# IO_Peripherals.net
KiCad netlist of a schematic drawn in Altium Designer
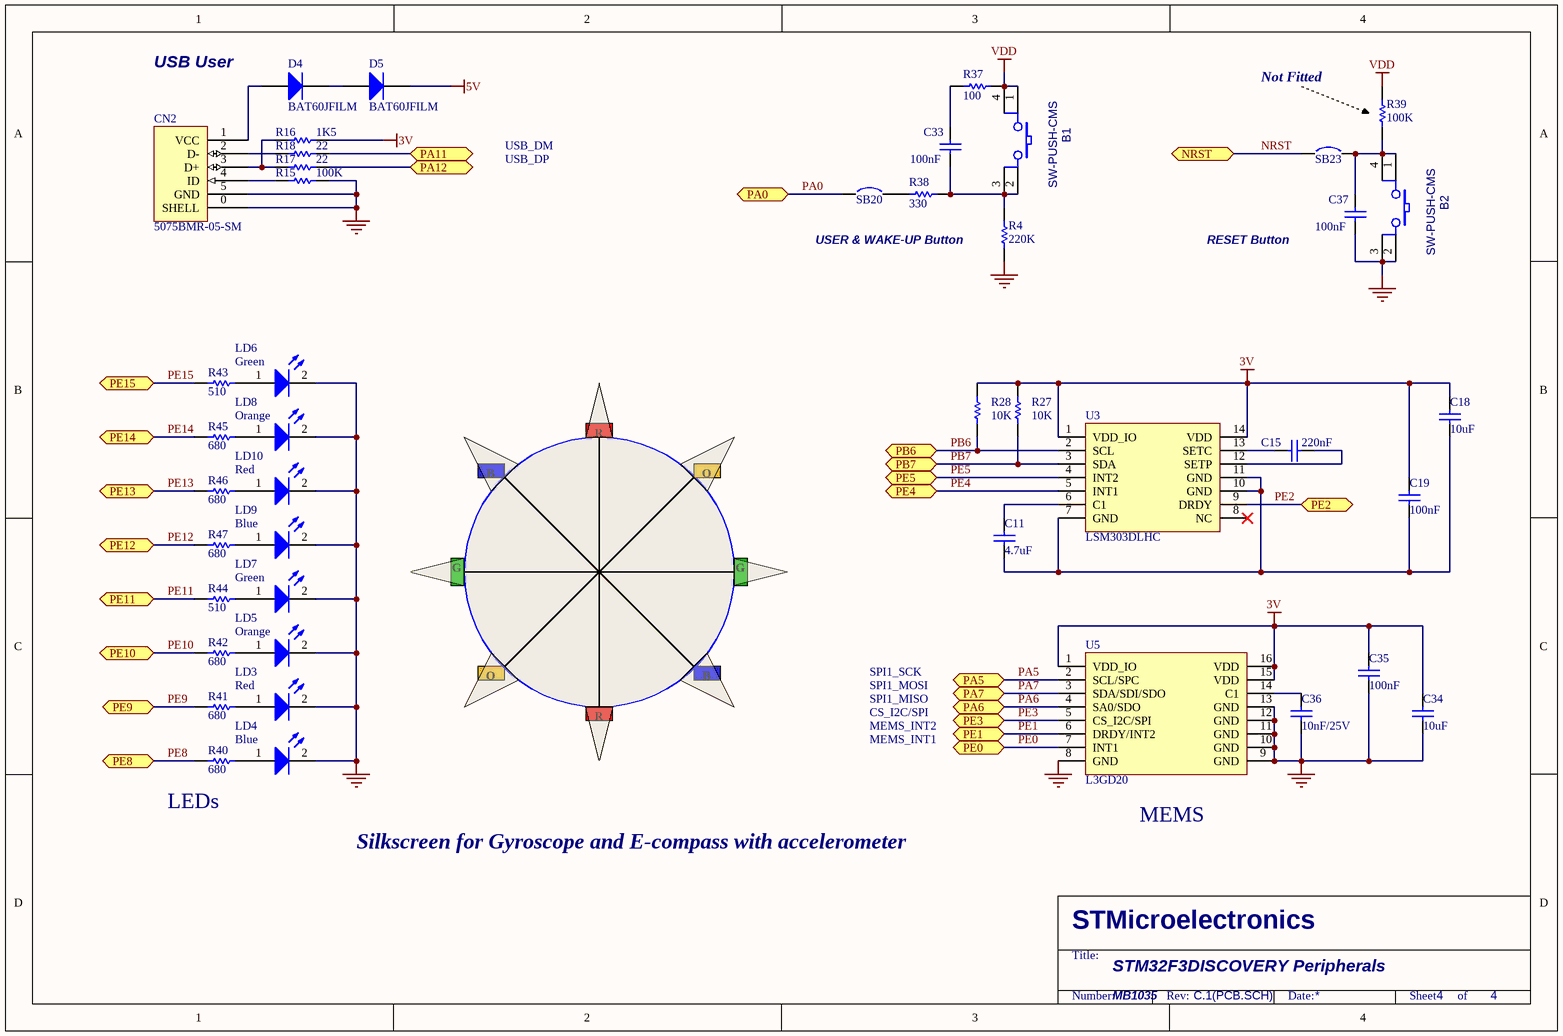
[diagram p0: IO Peripherals.SchDoc]

(export (version "E")
  (design (tool "Eeschema 10.0.6"))
  (components
    (comp (ref "B1")
      (value "SW-PUSH-CMS")
      (footprint "BP1CMS")
      (description "Non-Open Push-Button 0.1A 24V")
      (libsource (lib "MB913_1") (part "SW-PUSH-CMS"))
    )
    (comp (ref "B2")
      (value "SW-PUSH-CMS")
      (footprint "BP1CMS")
      (description "Non-Open Push-Button 0.1A 24V")
      (libsource (lib "MB913_1") (part "SW-PUSH-CMS"))
    )
    (comp (ref "C11")
      (value "4.7uF")
      (footprint "0603C")
      (description "Capacitor")
      (fields (field (name "PUBLISHER") "Altium Limited"))
      (libsource (lib "Miscellaneous Devices") (part "CAP"))
    )
    (comp (ref "C15")
      (value "220nF")
      (footprint "0603C")
      (description "Capacitor")
      (fields (field (name "PUBLISHER") "Altium Limited"))
      (libsource (lib "Miscellaneous Devices") (part "CAP"))
    )
    (comp (ref "C18")
      (value "10uF")
      (footprint "0603C")
      (description "Capacitor")
      (fields (field (name "PUBLISHER") "Altium Limited"))
      (libsource (lib "Miscellaneous Devices") (part "CAP"))
    )
    (comp (ref "C19")
      (value "100nF")
      (footprint "0603C")
      (description "Capacitor")
      (fields (field (name "PUBLISHER") "Altium Limited"))
      (libsource (lib "Miscellaneous Devices") (part "CAP"))
    )
    (comp (ref "C33")
      (value "100nF")
      (footprint "0603C")
      (description "Capacitor")
      (fields (field (name "PUBLISHER") "Altium Limited"))
      (libsource (lib "Miscellaneous Devices") (part "CAP"))
    )
    (comp (ref "C34")
      (value "10uF")
      (footprint "0603C")
      (description "Capacitor")
      (fields (field (name "PUBLISHER") "Altium Limited"))
      (libsource (lib "Miscellaneous Devices") (part "CAP"))
    )
    (comp (ref "C35")
      (value "100nF")
      (footprint "0603C")
      (description "Capacitor")
      (fields (field (name "PUBLISHER") "Altium Limited"))
      (libsource (lib "Miscellaneous Devices") (part "CAP"))
    )
    (comp (ref "C36")
      (value "10nF/25V")
      (footprint "0603C")
      (description "Capacitor")
      (fields (field (name "PUBLISHER") "Altium Limited"))
      (libsource (lib "Miscellaneous Devices") (part "CAP"))
    )
    (comp (ref "C37")
      (value "100nF")
      (footprint "0603C")
      (description "Capacitor")
      (fields (field (name "PUBLISHER") "Altium Limited"))
      (libsource (lib "Miscellaneous Devices") (part "CAP"))
    )
    (comp (ref "CN2")
      (value "5075BMR-05-SM")
      (footprint "USB-MINI-B-SMD")
      (libsource (lib "MCD_TOOLS") (part "USB-MINI-typeB connector"))
    )
    (comp (ref "D4")
      (value "BAT60JFILM")
      (footprint "SOD323/A")
      (fields (field (name "PUBLISHER") "Altium Limited"))
      (libsource (lib "MB997") (part "BAT60JFILM"))
    )
    (comp (ref "D5")
      (value "BAT60JFILM")
      (footprint "SOD323/A")
      (fields (field (name "PUBLISHER") "Altium Limited"))
      (libsource (lib "MB997") (part "BAT60JFILM"))
    )
    (comp (ref "LD3")
      (value "Red")
      (footprint "0603D")
      (description "Typical RED, GREEN, YELLOW, AMBER GaAs LED")
      (fields (field (name "PUBLISHER") "Altium Limited"))
      (libsource (lib "Miscellaneous Devices") (part "LED2"))
    )
    (comp (ref "LD4")
      (value "Blue")
      (footprint "0603D")
      (description "Typical RED, GREEN, YELLOW, AMBER GaAs LED")
      (fields (field (name "PUBLISHER") "Altium Limited"))
      (libsource (lib "Miscellaneous Devices") (part "LED2"))
    )
    (comp (ref "LD5")
      (value "Orange")
      (footprint "0603D")
      (description "Typical RED, GREEN, YELLOW, AMBER GaAs LED")
      (fields (field (name "PUBLISHER") "Altium Limited"))
      (libsource (lib "Miscellaneous Devices") (part "LED2"))
    )
    (comp (ref "LD6")
      (value "Green")
      (footprint "0603D")
      (description "Typical RED, GREEN, YELLOW, AMBER GaAs LED")
      (fields (field (name "PUBLISHER") "Altium Limited"))
      (libsource (lib "Miscellaneous Devices") (part "LED2"))
    )
    (comp (ref "LD7")
      (value "Green")
      (footprint "0603D")
      (description "Typical RED, GREEN, YELLOW, AMBER GaAs LED")
      (fields (field (name "PUBLISHER") "Altium Limited"))
      (libsource (lib "Miscellaneous Devices") (part "LED2"))
    )
    (comp (ref "LD8")
      (value "Orange")
      (footprint "0603D")
      (description "Typical RED, GREEN, YELLOW, AMBER GaAs LED")
      (fields (field (name "PUBLISHER") "Altium Limited"))
      (libsource (lib "Miscellaneous Devices") (part "LED2"))
    )
    (comp (ref "LD9")
      (value "Blue")
      (footprint "0603D")
      (description "Typical RED, GREEN, YELLOW, AMBER GaAs LED")
      (fields (field (name "PUBLISHER") "Altium Limited"))
      (libsource (lib "Miscellaneous Devices") (part "LED2"))
    )
    (comp (ref "LD10")
      (value "Red")
      (footprint "0603D")
      (description "Typical RED, GREEN, YELLOW, AMBER GaAs LED")
      (fields (field (name "PUBLISHER") "Altium Limited"))
      (libsource (lib "Miscellaneous Devices") (part "LED2"))
    )
    (comp (ref "R4")
      (value "220K")
      (description "Resistor")
      (fields (field (name "PUBLISHER") "Altium Limited"))
      (libsource (lib "Miscellaneous Devices") (part "res1"))
    )
    (comp (ref "R15")
      (value "100K")
      (footprint "0402R")
      (description "Resistor")
      (fields (field (name "PUBLISHER") "Altium Limited"))
      (libsource (lib "MB915_1") (part "res1"))
    )
    (comp (ref "R16")
      (value "1K5")
      (footprint "0402R")
      (description "Resistor")
      (fields (field (name "PUBLISHER") "Altium Limited"))
      (libsource (lib "MB915_1") (part "res1"))
    )
    (comp (ref "R17")
      (value "22")
      (footprint "0402R")
      (description "Resistor")
      (fields (field (name "PUBLISHER") "Altium Limited"))
      (libsource (lib "MB915_1") (part "res1"))
    )
    (comp (ref "R18")
      (value "22")
      (footprint "0402R")
      (description "Resistor")
      (fields (field (name "PUBLISHER") "Altium Limited"))
      (libsource (lib "MB915_1") (part "res1"))
    )
    (comp (ref "R27")
      (value "10K")
      (footprint "0402R")
      (description "Resistor")
      (fields (field (name "PUBLISHER") "Altium Limited"))
      (libsource (lib "Miscellaneous Devices") (part "res1"))
    )
    (comp (ref "R28")
      (value "10K")
      (footprint "0402R")
      (description "Resistor")
      (fields (field (name "PUBLISHER") "Altium Limited"))
      (libsource (lib "Miscellaneous Devices") (part "res1"))
    )
    (comp (ref "R37")
      (value "100")
      (footprint "0402R")
      (description "Resistor")
      (fields (field (name "PUBLISHER") "Altium Limited"))
      (libsource (lib "Miscellaneous Devices") (part "res1"))
    )
    (comp (ref "R38")
      (value "330")
      (footprint "0402R")
      (description "Resistor")
      (fields (field (name "PUBLISHER") "Altium Limited"))
      (libsource (lib "Miscellaneous Devices") (part "res1"))
    )
    (comp (ref "R39")
      (value "100K")
      (footprint "0402R")
      (description "Resistor")
      (fields (field (name "PUBLISHER") "Altium Limited"))
      (libsource (lib "Miscellaneous Devices") (part "res1"))
    )
    (comp (ref "R40")
      (value "680")
      (footprint "0603R")
      (description "Resistor")
      (fields (field (name "PUBLISHER") "Altium Limited"))
      (libsource (lib "Miscellaneous Devices") (part "Res1"))
    )
    (comp (ref "R41")
      (value "680")
      (footprint "0603R")
      (description "Resistor")
      (fields (field (name "PUBLISHER") "Altium Limited"))
      (libsource (lib "Miscellaneous Devices") (part "Res1"))
    )
    (comp (ref "R42")
      (value "680")
      (footprint "0603R")
      (description "Resistor")
      (fields (field (name "PUBLISHER") "Altium Limited"))
      (libsource (lib "Miscellaneous Devices") (part "Res1"))
    )
    (comp (ref "R43")
      (value "510")
      (footprint "0603R")
      (description "Resistor")
      (fields (field (name "PUBLISHER") "Altium Limited"))
      (libsource (lib "Miscellaneous Devices") (part "Res1"))
    )
    (comp (ref "R44")
      (value "510")
      (footprint "0603R")
      (description "Resistor")
      (fields (field (name "PUBLISHER") "Altium Limited"))
      (libsource (lib "Miscellaneous Devices") (part "Res1"))
    )
    (comp (ref "R45")
      (value "680")
      (footprint "0603R")
      (description "Resistor")
      (fields (field (name "PUBLISHER") "Altium Limited"))
      (libsource (lib "Miscellaneous Devices") (part "Res1"))
    )
    (comp (ref "R46")
      (value "680")
      (footprint "0603R")
      (description "Resistor")
      (fields (field (name "PUBLISHER") "Altium Limited"))
      (libsource (lib "Miscellaneous Devices") (part "Res1"))
    )
    (comp (ref "R47")
      (value "680")
      (footprint "0603R")
      (description "Resistor")
      (fields (field (name "PUBLISHER") "Altium Limited"))
      (libsource (lib "Miscellaneous Devices") (part "Res1"))
    )
    (comp (ref "SB20")
      (value "Circuit Breaker")
      (footprint "JP2_SMD")
      (fields (field (name "PUBLISHER") "Altium Limited"))
      (libsource (lib "MB915") (part "Circuit Breaker"))
    )
    (comp (ref "SB23")
      (value "Circuit Breaker")
      (footprint "JP2_SMD")
      (fields (field (name "PUBLISHER") "Altium Limited"))
      (libsource (lib "MB915") (part "Circuit Breaker"))
    )
    (comp (ref "U3")
      (value "LSM303DLHC")
      (footprint "LGA14")
      (description "Ultra compact high performance e-compass 3D accelerometer and 3D magnetometer module")
      (libsource (lib "MCD_TOOLS") (part "LSM303DLHC"))
    )
    (comp (ref "U5")
      (value "L3GD20")
      (footprint "LGA16")
      (description "MEMS motion sensor three-axis digital output gyroscopeelerometer")
      (libsource (lib "MCD_TOOLS") (part "L3GD20"))
    )
  )
  (nets
    (net (code "1") (name "/NRST") (class "Default")
      (node (ref "SB23") (pin "1") (pinfunction "1_1") (pintype "passive"))
    )
    (net (code "2") (name "/PA0") (class "Default")
      (node (ref "SB20") (pin "1") (pinfunction "1_1") (pintype "passive"))
    )
    (net (code "3") (name "/PA5") (class "Default")
      (node (ref "U5") (pin "2") (pinfunction "SCL/SPC_2") (pintype "passive"))
    )
    (net (code "4") (name "/PA6") (class "Default")
      (node (ref "U5") (pin "4") (pinfunction "SA0/SDO_4") (pintype "passive"))
    )
    (net (code "5") (name "/PA7") (class "Default")
      (node (ref "U5") (pin "3") (pinfunction "SDA/SDI/SDO_3") (pintype "passive"))
    )
    (net (code "6") (name "/PA11") (class "Default")
      (node (ref "R18") (pin "2") (pinfunction "2_2") (pintype "passive"))
    )
    (net (code "7") (name "/PA12") (class "Default")
      (node (ref "R17") (pin "2") (pinfunction "2_2") (pintype "passive"))
    )
    (net (code "8") (name "/PB6") (class "Default")
      (node (ref "R28") (pin "2") (pinfunction "2_2") (pintype "passive"))
      (node (ref "U3") (pin "2") (pinfunction "SCL_2") (pintype "passive"))
    )
    (net (code "9") (name "/PB7") (class "Default")
      (node (ref "R27") (pin "2") (pinfunction "2_2") (pintype "passive"))
      (node (ref "U3") (pin "3") (pinfunction "SDA_3") (pintype "passive"))
    )
    (net (code "10") (name "/PE0") (class "Default")
      (node (ref "U5") (pin "7") (pinfunction "INT1_7") (pintype "passive"))
    )
    (net (code "11") (name "/PE1") (class "Default")
      (node (ref "U5") (pin "6") (pinfunction "DRDY/INT2_6") (pintype "passive"))
    )
    (net (code "12") (name "/PE2") (class "Default")
      (node (ref "U3") (pin "9") (pinfunction "DRDY_9") (pintype "passive"))
    )
    (net (code "13") (name "/PE3") (class "Default")
      (node (ref "U5") (pin "5") (pinfunction "CS_I2C/SPI_5") (pintype "passive"))
    )
    (net (code "14") (name "/PE4") (class "Default")
      (node (ref "U3") (pin "5") (pinfunction "INT1_5") (pintype "passive"))
    )
    (net (code "15") (name "/PE5") (class "Default")
      (node (ref "U3") (pin "4") (pinfunction "INT2_4") (pintype "passive"))
    )
    (net (code "16") (name "/PE8") (class "Default")
      (node (ref "R40") (pin "2") (pinfunction "2_2") (pintype "passive"))
    )
    (net (code "17") (name "/PE9") (class "Default")
      (node (ref "R41") (pin "2") (pinfunction "2_2") (pintype "passive"))
    )
    (net (code "18") (name "/PE10") (class "Default")
      (node (ref "R42") (pin "2") (pinfunction "2_2") (pintype "passive"))
    )
    (net (code "19") (name "/PE11") (class "Default")
      (node (ref "R44") (pin "2") (pinfunction "2_2") (pintype "passive"))
    )
    (net (code "20") (name "/PE12") (class "Default")
      (node (ref "R47") (pin "2") (pinfunction "2_2") (pintype "passive"))
    )
    (net (code "21") (name "/PE13") (class "Default")
      (node (ref "R46") (pin "2") (pinfunction "2_2") (pintype "passive"))
    )
    (net (code "22") (name "/PE14") (class "Default")
      (node (ref "R45") (pin "2") (pinfunction "2_2") (pintype "passive"))
    )
    (net (code "23") (name "/PE15") (class "Default")
      (node (ref "R43") (pin "2") (pinfunction "2_2") (pintype "passive"))
    )
    (net (code "24") (name "3V") (class "Default")
      (node (ref "C18") (pin "2") (pinfunction "2_2") (pintype "passive"))
      (node (ref "C19") (pin "2") (pinfunction "2_2") (pintype "passive"))
      (node (ref "C34") (pin "2") (pinfunction "2_2") (pintype "passive"))
      (node (ref "C35") (pin "2") (pinfunction "2_2") (pintype "passive"))
      (node (ref "R16") (pin "2") (pinfunction "2_2") (pintype "passive"))
      (node (ref "R27") (pin "1") (pinfunction "1_1") (pintype "passive"))
      (node (ref "R28") (pin "1") (pinfunction "1_1") (pintype "passive"))
      (node (ref "U3") (pin "1") (pinfunction "VDD_IO_1") (pintype "passive"))
      (node (ref "U3") (pin "14") (pinfunction "VDD_14") (pintype "passive"))
      (node (ref "U5") (pin "1") (pinfunction "VDD_IO_1") (pintype "passive"))
      (node (ref "U5") (pin "15") (pinfunction "VDD_15") (pintype "passive"))
      (node (ref "U5") (pin "16") (pinfunction "VDD_16") (pintype "passive"))
    )
    (net (code "25") (name "5V") (class "Default")
      (node (ref "D5") (pin "2") (pinfunction "K_2") (pintype "passive"))
    )
    (net (code "26") (name "GND") (class "Default")
      (node (ref "B2") (pin "2") (pinfunction "2_2") (pintype "passive"))
      (node (ref "B2") (pin "3") (pinfunction "3_3") (pintype "passive"))
      (node (ref "C34") (pin "1") (pinfunction "1_1") (pintype "passive"))
      (node (ref "C35") (pin "1") (pinfunction "1_1") (pintype "passive"))
      (node (ref "C36") (pin "1") (pinfunction "1_1") (pintype "passive"))
      (node (ref "C37") (pin "1") (pinfunction "1_1") (pintype "passive"))
      (node (ref "CN2") (pin "0") (pinfunction "SHELL_0") (pintype "power_in"))
      (node (ref "CN2") (pin "5") (pinfunction "GND_5") (pintype "power_in"))
      (node (ref "LD10") (pin "2") (pinfunction "K_2") (pintype "passive"))
      (node (ref "LD3") (pin "2") (pinfunction "K_2") (pintype "passive"))
      (node (ref "LD4") (pin "2") (pinfunction "K_2") (pintype "passive"))
      (node (ref "LD5") (pin "2") (pinfunction "K_2") (pintype "passive"))
      (node (ref "LD6") (pin "2") (pinfunction "K_2") (pintype "passive"))
      (node (ref "LD7") (pin "2") (pinfunction "K_2") (pintype "passive"))
      (node (ref "LD8") (pin "2") (pinfunction "K_2") (pintype "passive"))
      (node (ref "LD9") (pin "2") (pinfunction "K_2") (pintype "passive"))
      (node (ref "R15") (pin "2") (pinfunction "2_2") (pintype "passive"))
      (node (ref "R4") (pin "1") (pinfunction "1_1") (pintype "passive"))
      (node (ref "U5") (pin "10") (pinfunction "GND_10") (pintype "passive"))
      (node (ref "U5") (pin "11") (pinfunction "GND_11") (pintype "passive"))
      (node (ref "U5") (pin "12") (pinfunction "GND_12") (pintype "passive"))
      (node (ref "U5") (pin "13") (pinfunction "GND_13") (pintype "passive"))
      (node (ref "U5") (pin "8") (pinfunction "GND_8") (pintype "passive"))
      (node (ref "U5") (pin "9") (pinfunction "GND_9") (pintype "passive"))
    )
    (net (code "27") (name "Net-(B1-Pad2)") (class "Default")
      (node (ref "B1") (pin "2") (pinfunction "2_2") (pintype "passive"))
      (node (ref "B1") (pin "3") (pinfunction "3_3") (pintype "passive"))
      (node (ref "C33") (pin "1") (pinfunction "1_1") (pintype "passive"))
      (node (ref "R38") (pin "2") (pinfunction "2_2") (pintype "passive"))
      (node (ref "R4") (pin "2") (pinfunction "2_2") (pintype "passive"))
    )
    (net (code "28") (name "Net-(B2-Pad1)") (class "Default")
      (node (ref "B2") (pin "1") (pinfunction "1_1") (pintype "passive"))
      (node (ref "B2") (pin "4") (pinfunction "4_4") (pintype "passive"))
      (node (ref "C37") (pin "2") (pinfunction "2_2") (pintype "passive"))
      (node (ref "R39") (pin "1") (pinfunction "1_1") (pintype "passive"))
      (node (ref "SB23") (pin "2") (pinfunction "2_2") (pintype "passive"))
    )
    (net (code "29") (name "Net-(C11-Pad1)") (class "Default")
      (node (ref "C11") (pin "1") (pinfunction "1_1") (pintype "passive"))
      (node (ref "C18") (pin "1") (pinfunction "1_1") (pintype "passive"))
      (node (ref "C19") (pin "1") (pinfunction "1_1") (pintype "passive"))
      (node (ref "U3") (pin "10") (pinfunction "GND_10") (pintype "passive"))
      (node (ref "U3") (pin "11") (pinfunction "GND_11") (pintype "passive"))
      (node (ref "U3") (pin "7") (pinfunction "GND_7") (pintype "passive"))
    )
    (net (code "30") (name "Net-(C33-Pad2)") (class "Default")
      (node (ref "C33") (pin "2") (pinfunction "2_2") (pintype "passive"))
      (node (ref "R37") (pin "1") (pinfunction "1_1") (pintype "passive"))
    )
    (net (code "31") (name "Net-(CN2-D+)") (class "Default")
      (node (ref "CN2") (pin "3") (pinfunction "D+_3") (pintype "bidirectional"))
      (node (ref "R16") (pin "1") (pinfunction "1_1") (pintype "passive"))
      (node (ref "R17") (pin "1") (pinfunction "1_1") (pintype "passive"))
    )
    (net (code "32") (name "Net-(CN2-D-)") (class "Default")
      (node (ref "CN2") (pin "2") (pinfunction "D-_2") (pintype "bidirectional"))
      (node (ref "R18") (pin "1") (pinfunction "1_1") (pintype "passive"))
    )
    (net (code "33") (name "Net-(CN2-ID)") (class "Default")
      (node (ref "CN2") (pin "4") (pinfunction "ID_4") (pintype "input"))
      (node (ref "R15") (pin "1") (pinfunction "1_1") (pintype "passive"))
    )
    (net (code "34") (name "Net-(CN2-VCC)") (class "Default")
      (node (ref "CN2") (pin "1") (pinfunction "VCC_1") (pintype "power_in"))
      (node (ref "D4") (pin "1") (pinfunction "A_1") (pintype "passive"))
    )
    (net (code "35") (name "Net-(D4-K)") (class "Default")
      (node (ref "D4") (pin "2") (pinfunction "K_2") (pintype "passive"))
      (node (ref "D5") (pin "1") (pinfunction "A_1") (pintype "passive"))
    )
    (net (code "36") (name "Net-(LD3-A)") (class "Default")
      (node (ref "LD3") (pin "1") (pinfunction "A_1") (pintype "passive"))
      (node (ref "R41") (pin "1") (pinfunction "1_1") (pintype "passive"))
    )
    (net (code "37") (name "Net-(LD4-A)") (class "Default")
      (node (ref "LD4") (pin "1") (pinfunction "A_1") (pintype "passive"))
      (node (ref "R40") (pin "1") (pinfunction "1_1") (pintype "passive"))
    )
    (net (code "38") (name "Net-(LD5-A)") (class "Default")
      (node (ref "LD5") (pin "1") (pinfunction "A_1") (pintype "passive"))
      (node (ref "R42") (pin "1") (pinfunction "1_1") (pintype "passive"))
    )
    (net (code "39") (name "Net-(LD6-A)") (class "Default")
      (node (ref "LD6") (pin "1") (pinfunction "A_1") (pintype "passive"))
      (node (ref "R43") (pin "1") (pinfunction "1_1") (pintype "passive"))
    )
    (net (code "40") (name "Net-(LD7-A)") (class "Default")
      (node (ref "LD7") (pin "1") (pinfunction "A_1") (pintype "passive"))
      (node (ref "R44") (pin "1") (pinfunction "1_1") (pintype "passive"))
    )
    (net (code "41") (name "Net-(LD8-A)") (class "Default")
      (node (ref "LD8") (pin "1") (pinfunction "A_1") (pintype "passive"))
      (node (ref "R45") (pin "1") (pinfunction "1_1") (pintype "passive"))
    )
    (net (code "42") (name "Net-(LD9-A)") (class "Default")
      (node (ref "LD9") (pin "1") (pinfunction "A_1") (pintype "passive"))
      (node (ref "R47") (pin "1") (pinfunction "1_1") (pintype "passive"))
    )
    (net (code "43") (name "Net-(LD10-A)") (class "Default")
      (node (ref "LD10") (pin "1") (pinfunction "A_1") (pintype "passive"))
      (node (ref "R46") (pin "1") (pinfunction "1_1") (pintype "passive"))
    )
    (net (code "44") (name "Net-(R38-Pad1)") (class "Default")
      (node (ref "R38") (pin "1") (pinfunction "1_1") (pintype "passive"))
      (node (ref "SB20") (pin "2") (pinfunction "2_2") (pintype "passive"))
    )
    (net (code "45") (name "Net-(U3-C1)") (class "Default")
      (node (ref "C11") (pin "2") (pinfunction "2_2") (pintype "passive"))
      (node (ref "U3") (pin "6") (pinfunction "C1_6") (pintype "passive"))
    )
    (net (code "46") (name "Net-(U3-SETC)") (class "Default")
      (node (ref "C15") (pin "1") (pinfunction "1_1") (pintype "passive"))
      (node (ref "U3") (pin "13") (pinfunction "SETC_13") (pintype "passive"))
    )
    (net (code "47") (name "Net-(U3-SETP)") (class "Default")
      (node (ref "C15") (pin "2") (pinfunction "2_2") (pintype "passive"))
      (node (ref "U3") (pin "12") (pinfunction "SETP_12") (pintype "passive"))
    )
    (net (code "48") (name "Net-(U5-C1)") (class "Default")
      (node (ref "C36") (pin "2") (pinfunction "2_2") (pintype "passive"))
      (node (ref "U5") (pin "14") (pinfunction "C1_14") (pintype "passive"))
    )
    (net (code "49") (name "VDD") (class "Default")
      (node (ref "B1") (pin "1") (pinfunction "1_1") (pintype "passive"))
      (node (ref "B1") (pin "4") (pinfunction "4_4") (pintype "passive"))
      (node (ref "R37") (pin "2") (pinfunction "2_2") (pintype "passive"))
      (node (ref "R39") (pin "2") (pinfunction "2_2") (pintype "passive"))
    )
    (net (code "50") (name "unconnected-(U3-NC-Pad8)") (class "Default")
      (node (ref "U3") (pin "8") (pinfunction "NC_8") (pintype "passive+no_connect"))
    )
  )
)
